# IO_LED.net
KiCad netlist of a schematic drawn in Altium Designer
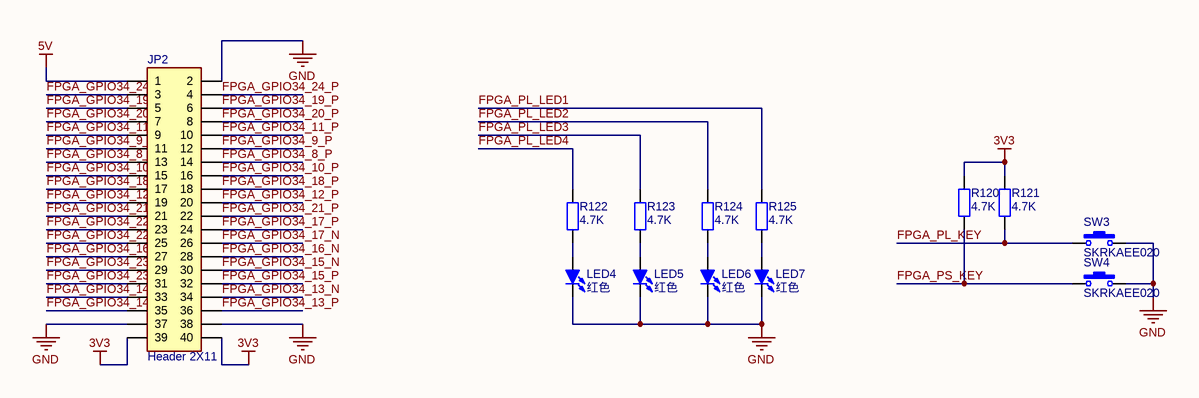
[diagram p0: IO_LED.SchDoc]

(export (version "E")
  (design (tool "Eeschema 10.0.6"))
  (components
    (comp (ref "JP2")
      (value "Header 2X11")
      (footprint "IDC2.54-LI-2x20P")
      (description "20*2P接插件")
      (fields (field (name "版权归属") "源创客"))
      (libsource (lib "4.5   - 接插件-脚距2.54") (part "Header 20X2"))
    )
    (comp (ref "LED4")
      (value "红色")
      (footprint "LED 0805G")
      (description "贴片LED")
      (fields (field (name "版权归属") "源创客"))
      (libsource (lib "9.1   - LED") (part "LED-SMD"))
    )
    (comp (ref "LED5")
      (value "红色")
      (footprint "LED 0805G")
      (description "贴片LED")
      (fields (field (name "版权归属") "源创客"))
      (libsource (lib "9.1   - LED") (part "LED-SMD"))
    )
    (comp (ref "LED6")
      (value "红色")
      (footprint "LED 0805G")
      (description "贴片LED")
      (fields (field (name "版权归属") "源创客"))
      (libsource (lib "9.1   - LED") (part "LED-SMD"))
    )
    (comp (ref "LED7")
      (value "红色")
      (footprint "LED 0805G")
      (description "贴片LED")
      (fields (field (name "版权归属") "源创客"))
      (libsource (lib "9.1   - LED") (part "LED-SMD"))
    )
    (comp (ref "R120")
      (value "4.7K")
      (footprint "R 0402_L")
      (description "贴片电阻")
      (fields (field (name "版权归属") "源创客"))
      (libsource (lib "3.1   - 电阻-电容-电感") (part "R"))
    )
    (comp (ref "R121")
      (value "4.7K")
      (footprint "R 0402_L")
      (description "贴片电阻")
      (fields (field (name "版权归属") "源创客"))
      (libsource (lib "3.1   - 电阻-电容-电感") (part "R"))
    )
    (comp (ref "R122")
      (value "4.7K")
      (footprint "R 0402_L")
      (description "贴片电阻")
      (fields (field (name "版权归属") "源创客"))
      (libsource (lib "3.1   - 电阻-电容-电感") (part "R"))
    )
    (comp (ref "R123")
      (value "4.7K")
      (footprint "R 0402_L")
      (description "贴片电阻")
      (fields (field (name "版权归属") "源创客"))
      (libsource (lib "3.1   - 电阻-电容-电感") (part "R"))
    )
    (comp (ref "R124")
      (value "4.7K")
      (footprint "R 0402_L")
      (description "贴片电阻")
      (fields (field (name "版权归属") "源创客"))
      (libsource (lib "3.1   - 电阻-电容-电感") (part "R"))
    )
    (comp (ref "R125")
      (value "4.7K")
      (footprint "R 0402_L")
      (description "贴片电阻")
      (fields (field (name "版权归属") "源创客"))
      (libsource (lib "3.1   - 电阻-电容-电感") (part "R"))
    )
    (comp (ref "SW3")
      (value "SKRKAEE020")
      (footprint "SKRKAEE020")
      (description "2.9x3.9轻触开关")
      (libsource (lib "0.5 - 按键_开关_蜂鸣器_保险丝_电池_测试点_Mark点_铜柱") (part "SKRKAEE020"))
    )
    (comp (ref "SW4")
      (value "SKRKAEE020")
      (footprint "SKRKAEE020")
      (description "2.9x3.9轻触开关")
      (libsource (lib "0.5 - 按键_开关_蜂鸣器_保险丝_电池_测试点_Mark点_铜柱") (part "SKRKAEE020"))
    )
  )
  (nets
    (net (code "1") (name "/FPGA_GPIO34_8_N") (class "Default")
      (node (ref "JP2") (pin "13") (pinfunction "13_13") (pintype "passive"))
    )
    (net (code "2") (name "/FPGA_GPIO34_8_P") (class "Default")
      (node (ref "JP2") (pin "14") (pinfunction "14_14") (pintype "passive"))
    )
    (net (code "3") (name "/FPGA_GPIO34_9_N") (class "Default")
      (node (ref "JP2") (pin "11") (pinfunction "11_11") (pintype "passive"))
    )
    (net (code "4") (name "/FPGA_GPIO34_9_P") (class "Default")
      (node (ref "JP2") (pin "12") (pinfunction "12_12") (pintype "passive"))
    )
    (net (code "5") (name "/FPGA_GPIO34_10_N") (class "Default")
      (node (ref "JP2") (pin "15") (pinfunction "15_15") (pintype "passive"))
    )
    (net (code "6") (name "/FPGA_GPIO34_10_P") (class "Default")
      (node (ref "JP2") (pin "16") (pinfunction "16_16") (pintype "passive"))
    )
    (net (code "7") (name "/FPGA_GPIO34_11_N") (class "Default")
      (node (ref "JP2") (pin "9") (pinfunction "9_9") (pintype "passive"))
    )
    (net (code "8") (name "/FPGA_GPIO34_11_P") (class "Default")
      (node (ref "JP2") (pin "10") (pinfunction "10_10") (pintype "passive"))
    )
    (net (code "9") (name "/FPGA_GPIO34_12_N") (class "Default")
      (node (ref "JP2") (pin "19") (pinfunction "19_19") (pintype "passive"))
    )
    (net (code "10") (name "/FPGA_GPIO34_12_P") (class "Default")
      (node (ref "JP2") (pin "20") (pinfunction "20_20") (pintype "passive"))
    )
    (net (code "11") (name "/FPGA_GPIO34_13_N") (class "Default")
      (node (ref "JP2") (pin "34") (pinfunction "34_34") (pintype "passive"))
    )
    (net (code "12") (name "/FPGA_GPIO34_13_P") (class "Default")
      (node (ref "JP2") (pin "36") (pinfunction "36_36") (pintype "passive"))
    )
    (net (code "13") (name "/FPGA_GPIO34_14_N") (class "Default")
      (node (ref "JP2") (pin "33") (pinfunction "33_33") (pintype "passive"))
    )
    (net (code "14") (name "/FPGA_GPIO34_14_P") (class "Default")
      (node (ref "JP2") (pin "35") (pinfunction "35_35") (pintype "passive"))
    )
    (net (code "15") (name "/FPGA_GPIO34_15_N") (class "Default")
      (node (ref "JP2") (pin "30") (pinfunction "30_30") (pintype "passive"))
    )
    (net (code "16") (name "/FPGA_GPIO34_15_P") (class "Default")
      (node (ref "JP2") (pin "32") (pinfunction "32_32") (pintype "passive"))
    )
    (net (code "17") (name "/FPGA_GPIO34_16_N") (class "Default")
      (node (ref "JP2") (pin "28") (pinfunction "28_28") (pintype "passive"))
    )
    (net (code "18") (name "/FPGA_GPIO34_16_P") (class "Default")
      (node (ref "JP2") (pin "27") (pinfunction "27_27") (pintype "passive"))
    )
    (net (code "19") (name "/FPGA_GPIO34_17_N") (class "Default")
      (node (ref "JP2") (pin "26") (pinfunction "26_26") (pintype "passive"))
    )
    (net (code "20") (name "/FPGA_GPIO34_17_P") (class "Default")
      (node (ref "JP2") (pin "24") (pinfunction "24_24") (pintype "passive"))
    )
    (net (code "21") (name "/FPGA_GPIO34_18_N") (class "Default")
      (node (ref "JP2") (pin "17") (pinfunction "17_17") (pintype "passive"))
    )
    (net (code "22") (name "/FPGA_GPIO34_18_P") (class "Default")
      (node (ref "JP2") (pin "18") (pinfunction "18_18") (pintype "passive"))
    )
    (net (code "23") (name "/FPGA_GPIO34_19_N") (class "Default")
      (node (ref "JP2") (pin "5") (pinfunction "5_5") (pintype "passive"))
    )
    (net (code "24") (name "/FPGA_GPIO34_19_P") (class "Default")
      (node (ref "JP2") (pin "6") (pinfunction "6_6") (pintype "passive"))
    )
    (net (code "25") (name "/FPGA_GPIO34_20_N") (class "Default")
      (node (ref "JP2") (pin "7") (pinfunction "7_7") (pintype "passive"))
    )
    (net (code "26") (name "/FPGA_GPIO34_20_P") (class "Default")
      (node (ref "JP2") (pin "8") (pinfunction "8_8") (pintype "passive"))
    )
    (net (code "27") (name "/FPGA_GPIO34_21_N") (class "Default")
      (node (ref "JP2") (pin "21") (pinfunction "21_21") (pintype "passive"))
    )
    (net (code "28") (name "/FPGA_GPIO34_21_P") (class "Default")
      (node (ref "JP2") (pin "22") (pinfunction "22_22") (pintype "passive"))
    )
    (net (code "29") (name "/FPGA_GPIO34_22_N") (class "Default")
      (node (ref "JP2") (pin "25") (pinfunction "25_25") (pintype "passive"))
    )
    (net (code "30") (name "/FPGA_GPIO34_22_P") (class "Default")
      (node (ref "JP2") (pin "23") (pinfunction "23_23") (pintype "passive"))
    )
    (net (code "31") (name "/FPGA_GPIO34_23_N") (class "Default")
      (node (ref "JP2") (pin "31") (pinfunction "31_31") (pintype "passive"))
    )
    (net (code "32") (name "/FPGA_GPIO34_23_P") (class "Default")
      (node (ref "JP2") (pin "29") (pinfunction "29_29") (pintype "passive"))
    )
    (net (code "33") (name "/FPGA_GPIO34_24_N") (class "Default")
      (node (ref "JP2") (pin "3") (pinfunction "3_3") (pintype "passive"))
    )
    (net (code "34") (name "/FPGA_GPIO34_24_P") (class "Default")
      (node (ref "JP2") (pin "4") (pinfunction "4_4") (pintype "passive"))
    )
    (net (code "35") (name "/FPGA_PL_KEY") (class "Default")
      (node (ref "R121") (pin "1") (pinfunction "1_1") (pintype "passive"))
      (node (ref "SW3") (pin "1") (pinfunction "1_1") (pintype "passive"))
    )
    (net (code "36") (name "/FPGA_PL_LED1") (class "Default")
      (node (ref "R125") (pin "2") (pinfunction "2_2") (pintype "passive"))
    )
    (net (code "37") (name "/FPGA_PL_LED2") (class "Default")
      (node (ref "R124") (pin "2") (pinfunction "2_2") (pintype "passive"))
    )
    (net (code "38") (name "/FPGA_PL_LED3") (class "Default")
      (node (ref "R123") (pin "2") (pinfunction "2_2") (pintype "passive"))
    )
    (net (code "39") (name "/FPGA_PL_LED4") (class "Default")
      (node (ref "R122") (pin "2") (pinfunction "2_2") (pintype "passive"))
    )
    (net (code "40") (name "/FPGA_PS_KEY") (class "Default")
      (node (ref "R120") (pin "1") (pinfunction "1_1") (pintype "passive"))
      (node (ref "SW4") (pin "1") (pinfunction "1_1") (pintype "passive"))
    )
    (net (code "41") (name "3V3") (class "Default")
      (node (ref "JP2") (pin "39") (pinfunction "39_39") (pintype "passive"))
      (node (ref "JP2") (pin "40") (pinfunction "40_40") (pintype "passive"))
      (node (ref "R120") (pin "2") (pinfunction "2_2") (pintype "passive"))
      (node (ref "R121") (pin "2") (pinfunction "2_2") (pintype "passive"))
    )
    (net (code "42") (name "5V") (class "Default")
      (node (ref "JP2") (pin "1") (pinfunction "1_1") (pintype "passive"))
    )
    (net (code "43") (name "GND") (class "Default")
      (node (ref "JP2") (pin "2") (pinfunction "2_2") (pintype "passive"))
      (node (ref "JP2") (pin "37") (pinfunction "37_37") (pintype "passive"))
      (node (ref "JP2") (pin "38") (pinfunction "38_38") (pintype "passive"))
      (node (ref "LED4") (pin "2") (pinfunction "K_2") (pintype "passive"))
      (node (ref "LED5") (pin "2") (pinfunction "K_2") (pintype "passive"))
      (node (ref "LED6") (pin "2") (pinfunction "K_2") (pintype "passive"))
      (node (ref "LED7") (pin "2") (pinfunction "K_2") (pintype "passive"))
      (node (ref "SW3") (pin "2") (pinfunction "2_2") (pintype "passive"))
      (node (ref "SW4") (pin "2") (pinfunction "2_2") (pintype "passive"))
    )
    (net (code "44") (name "Net-(LED4-A)") (class "Default")
      (node (ref "LED4") (pin "1") (pinfunction "A_1") (pintype "passive"))
      (node (ref "R122") (pin "1") (pinfunction "1_1") (pintype "passive"))
    )
    (net (code "45") (name "Net-(LED5-A)") (class "Default")
      (node (ref "LED5") (pin "1") (pinfunction "A_1") (pintype "passive"))
      (node (ref "R123") (pin "1") (pinfunction "1_1") (pintype "passive"))
    )
    (net (code "46") (name "Net-(LED6-A)") (class "Default")
      (node (ref "LED6") (pin "1") (pinfunction "A_1") (pintype "passive"))
      (node (ref "R124") (pin "1") (pinfunction "1_1") (pintype "passive"))
    )
    (net (code "47") (name "Net-(LED7-A)") (class "Default")
      (node (ref "LED7") (pin "1") (pinfunction "A_1") (pintype "passive"))
      (node (ref "R125") (pin "1") (pinfunction "1_1") (pintype "passive"))
    )
  )
)
